# DDMTD.net
KiCad netlist of a schematic drawn in Altium Designer
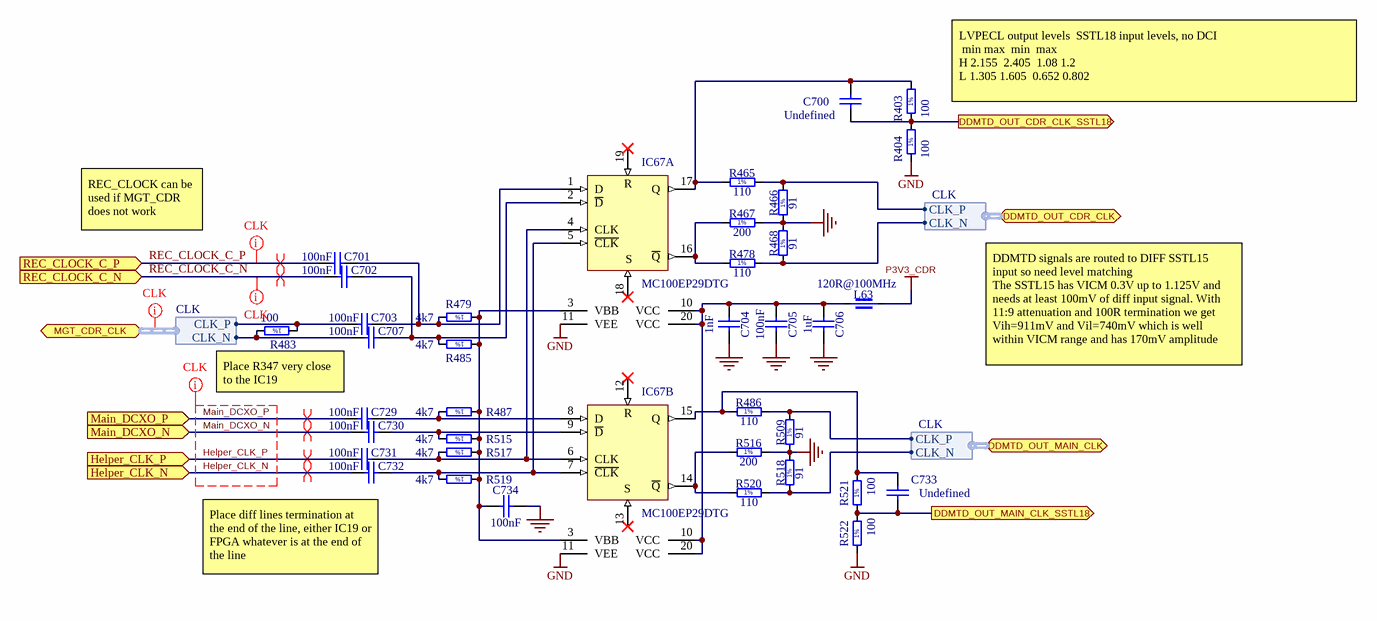
[diagram p0: DDMTD.SchDoc]

(export (version "E")
  (design (tool "Eeschema 10.0.6"))
  (components
    (comp (ref "C700")
      (value "Undefined")
      (footprint "CAPC1005X55N")
      (description "Non-polarised capacitor")
      (fields (field (name "PART NUMBER") "CC0402_NO-VALUE") (field (name "AUTHOR") "CERN DEM JLC"))
      (libsource (lib "Capacitors") (part "Capacitor - non polarized"))
    )
    (comp (ref "C701")
      (value "100nF")
      (footprint "CAPC1005X55N")
      (description "Non-polarised capacitor")
      (fields
        (field (name "MANUFACTURER PART NUMBER") "CC0402_100NF_16V_10%_X5R")
        (field (name "MANUFACTURER") "GENERIC")
        (field (name "AUTHOR") "CERN DEM JLC")
      )
      (libsource (lib "Capacitors") (part "Capacitor - non polarized"))
    )
    (comp (ref "C702")
      (value "100nF")
      (footprint "CAPC1005X55N")
      (description "Non-polarised capacitor")
      (fields
        (field (name "MANUFACTURER PART NUMBER") "CC0402_100NF_16V_10%_X5R")
        (field (name "MANUFACTURER") "GENERIC")
        (field (name "AUTHOR") "CERN DEM JLC")
      )
      (libsource (lib "Capacitors") (part "Capacitor - non polarized"))
    )
    (comp (ref "C703")
      (value "100nF")
      (footprint "CAPC1005X55N")
      (description "Non-polarised capacitor")
      (fields
        (field (name "MANUFACTURER PART NUMBER") "CC0402_100NF_16V_10%_X5R")
        (field (name "MANUFACTURER") "GENERIC")
        (field (name "AUTHOR") "CERN DEM JLC")
      )
      (libsource (lib "Capacitors") (part "Capacitor - non polarized"))
    )
    (comp (ref "C704")
      (value "1nF")
      (footprint "CAPC0603X33N")
      (description "Non-polarised capacitor")
      (fields
        (field (name "MANUFACTURER PART NUMBER") "CC0201_1NF_16V_10%_X5R")
        (field (name "MANUFACTURER") "GENERIC")
        (field (name "AUTHOR") "CERN DEM JLC")
      )
      (libsource (lib "Capacitors") (part "Capacitor - non polarized"))
    )
    (comp (ref "C705")
      (value "100nF")
      (footprint "CAPC0603X33N")
      (description "Non-polarised capacitor")
      (fields
        (field (name "MANUFACTURER PART NUMBER") "CC0201_100NF_6.3V_10%_X5R")
        (field (name "MANUFACTURER") "GENERIC")
        (field (name "AUTHOR") "CERN DEM JLC")
      )
      (libsource (lib "Capacitors") (part "Capacitor - non polarized"))
    )
    (comp (ref "C706")
      (value "1uF")
      (footprint "CAPC1005X55N")
      (description "Non-polarised capacitor")
      (fields
        (field (name "MANUFACTURER PART NUMBER") "CC0402_1UF_16V_10%_X5R")
        (field (name "MANUFACTURER") "GENERIC")
        (field (name "AUTHOR") "CERN DEM JLC")
      )
      (libsource (lib "Capacitors") (part "Capacitor - non polarized"))
    )
    (comp (ref "C707")
      (value "100nF")
      (footprint "CAPC1005X55N")
      (description "Non-polarised capacitor")
      (fields
        (field (name "MANUFACTURER PART NUMBER") "CC0402_100NF_16V_10%_X5R")
        (field (name "MANUFACTURER") "GENERIC")
        (field (name "AUTHOR") "CERN DEM JLC")
      )
      (libsource (lib "Capacitors") (part "Capacitor - non polarized"))
    )
    (comp (ref "C729")
      (value "100nF")
      (footprint "CAPC1005X55N")
      (description "Non-polarised capacitor")
      (fields
        (field (name "MANUFACTURER PART NUMBER") "CC0402_100NF_16V_10%_X5R")
        (field (name "MANUFACTURER") "GENERIC")
        (field (name "AUTHOR") "CERN DEM JLC")
      )
      (libsource (lib "Capacitors") (part "Capacitor - non polarized"))
    )
    (comp (ref "C730")
      (value "100nF")
      (footprint "CAPC1005X55N")
      (description "Non-polarised capacitor")
      (fields
        (field (name "MANUFACTURER PART NUMBER") "CC0402_100NF_16V_10%_X5R")
        (field (name "MANUFACTURER") "GENERIC")
        (field (name "AUTHOR") "CERN DEM JLC")
      )
      (libsource (lib "Capacitors") (part "Capacitor - non polarized"))
    )
    (comp (ref "C731")
      (value "100nF")
      (footprint "CAPC1005X55N")
      (description "Non-polarised capacitor")
      (fields
        (field (name "MANUFACTURER PART NUMBER") "CC0402_100NF_16V_10%_X5R")
        (field (name "MANUFACTURER") "GENERIC")
        (field (name "AUTHOR") "CERN DEM JLC")
      )
      (libsource (lib "Capacitors") (part "Capacitor - non polarized"))
    )
    (comp (ref "C732")
      (value "100nF")
      (footprint "CAPC1005X55N")
      (description "Non-polarised capacitor")
      (fields
        (field (name "MANUFACTURER PART NUMBER") "CC0402_100NF_16V_10%_X5R")
        (field (name "MANUFACTURER") "GENERIC")
        (field (name "AUTHOR") "CERN DEM JLC")
      )
      (libsource (lib "Capacitors") (part "Capacitor - non polarized"))
    )
    (comp (ref "C733")
      (value "Undefined")
      (footprint "CAPC1005X55N")
      (description "Non-polarised capacitor")
      (fields (field (name "PART NUMBER") "CC0402_NO-VALUE") (field (name "AUTHOR") "CERN DEM JLC"))
      (libsource (lib "Capacitors") (part "Capacitor - non polarized"))
    )
    (comp (ref "C734")
      (value "100nF")
      (footprint "CAPC0603X33N")
      (description "Non-polarised capacitor")
      (fields
        (field (name "MANUFACTURER PART NUMBER") "CC0201_100NF_6.3V_10%_X5R")
        (field (name "MANUFACTURER") "GENERIC")
        (field (name "AUTHOR") "CERN DEM JLC")
      )
      (libsource (lib "Capacitors") (part "Capacitor - non polarized"))
    )
    (comp (ref "IC67")
      (value "MC100EP29DTG")
      (footprint "SOP65P640X120-20N")
      (description "3.3V/5V ECL Dual Differential Data and Clock D Flip-Flop With Set and Reset")
      (fields (field (name "MANUFACTURER") "ON SEMICONDUCTOR") (field (name "AUTHOR") "CERN DEM JLC"))
      (libsource (lib "ICs And Semiconductors") (part "100EP29D"))
    )
    (comp (ref "L63")
      (value "120R@100MHz")
      (footprint "INDC1608X95N")
      (fields
        (field (name "MANUFACTURER PART NUMBER") "BLM18PG121SN1D")
        (field (name "MANUFACTURER") "MURATA")
        (field (name "PART NUMBER") "IND0603_MURATA_BLM18PG121SN1D")
        (field (name "AUTHOR") "CERN DEM BC")
      )
      (libsource (lib "Inductors & Transformers") (part "Ferrite Bead"))
    )
    (comp (ref "R403")
      (value "100")
      (footprint "RESC1005X40N")
      (description "Resistor - 1%")
      (fields
        (field (name "MANUFACTURER PART NUMBER") "R0402_100R_1%_0.0625W_100PPM")
        (field (name "MANUFACTURER") "GENERIC")
        (field (name "AUTHOR") "CERN DEM JLC")
      )
      (libsource (lib "Resistors") (part "Resistor - 1%"))
    )
    (comp (ref "R404")
      (value "100")
      (footprint "RESC1005X40N")
      (description "Resistor - 1%")
      (fields
        (field (name "MANUFACTURER PART NUMBER") "R0402_100R_1%_0.0625W_100PPM")
        (field (name "MANUFACTURER") "GENERIC")
        (field (name "AUTHOR") "CERN DEM JLC")
      )
      (libsource (lib "Resistors") (part "Resistor - 1%"))
    )
    (comp (ref "R465")
      (value "110")
      (footprint "RESC1005X40N")
      (description "Resistor - 1%")
      (fields
        (field (name "MANUFACTURER PART NUMBER") "R0402_110R_1%_0.0625W_100PPM")
        (field (name "MANUFACTURER") "GENERIC")
        (field (name "AUTHOR") "CERN DEM JLC")
      )
      (libsource (lib "Resistors") (part "Resistor - 1%"))
    )
    (comp (ref "R466")
      (value "91")
      (footprint "RESC1005X40N")
      (description "Resistor - 1%")
      (fields
        (field (name "MANUFACTURER PART NUMBER") "R0402_91R_1%_0.0625W_100PPM")
        (field (name "MANUFACTURER") "GENERIC")
        (field (name "AUTHOR") "CERN DEM JLC")
      )
      (libsource (lib "Resistors") (part "Resistor - 1%"))
    )
    (comp (ref "R467")
      (value "200")
      (footprint "RESC1005X40N")
      (description "Resistor - 1%")
      (fields
        (field (name "PART NUMBER") "R0402_200R_1%_0.0625W_100PPM")
        (field (name "POWER") "0.0625W")
        (field (name "AUTHOR") "CERN DEM JLC")
      )
      (libsource (lib "Resistors") (part "Resistor - 1%"))
    )
    (comp (ref "R468")
      (value "91")
      (footprint "RESC1005X40N")
      (description "Resistor - 1%")
      (fields
        (field (name "MANUFACTURER PART NUMBER") "R0402_91R_1%_0.0625W_100PPM")
        (field (name "MANUFACTURER") "GENERIC")
        (field (name "AUTHOR") "CERN DEM JLC")
      )
      (libsource (lib "Resistors") (part "Resistor - 1%"))
    )
    (comp (ref "R478")
      (value "110")
      (footprint "RESC1005X40N")
      (description "Resistor - 1%")
      (fields
        (field (name "MANUFACTURER PART NUMBER") "R0402_110R_1%_0.0625W_100PPM")
        (field (name "MANUFACTURER") "GENERIC")
        (field (name "AUTHOR") "CERN DEM JLC")
      )
      (libsource (lib "Resistors") (part "Resistor - 1%"))
    )
    (comp (ref "R479")
      (value "4k7")
      (footprint "RESC1005X40N")
      (description "Resistor - 1%")
      (fields
        (field (name "MANUFACTURER PART NUMBER") "R0402_4K7_1%_0.0625W_100PPM")
        (field (name "MANUFACTURER") "GENERIC")
        (field (name "AUTHOR") "CERN DEM JLC")
      )
      (libsource (lib "Resistors") (part "Resistor - 1%"))
    )
    (comp (ref "R483")
      (value "100")
      (footprint "RESC1005X40N")
      (description "Resistor - 1%")
      (fields
        (field (name "MANUFACTURER PART NUMBER") "R0402_100R_1%_0.0625W_100PPM")
        (field (name "MANUFACTURER") "GENERIC")
        (field (name "AUTHOR") "CERN DEM JLC")
      )
      (libsource (lib "Resistors") (part "Resistor - 1%"))
    )
    (comp (ref "R485")
      (value "4k7")
      (footprint "RESC1005X40N")
      (description "Resistor - 1%")
      (fields
        (field (name "MANUFACTURER PART NUMBER") "R0402_4K7_1%_0.0625W_100PPM")
        (field (name "MANUFACTURER") "GENERIC")
        (field (name "AUTHOR") "CERN DEM JLC")
      )
      (libsource (lib "Resistors") (part "Resistor - 1%"))
    )
    (comp (ref "R486")
      (value "110")
      (footprint "RESC1005X40N")
      (description "Resistor - 1%")
      (fields
        (field (name "MANUFACTURER PART NUMBER") "R0402_110R_1%_0.0625W_100PPM")
        (field (name "MANUFACTURER") "GENERIC")
        (field (name "AUTHOR") "CERN DEM JLC")
      )
      (libsource (lib "Resistors") (part "Resistor - 1%"))
    )
    (comp (ref "R487")
      (value "4k7")
      (footprint "RESC1005X40N")
      (description "Resistor - 1%")
      (fields
        (field (name "MANUFACTURER PART NUMBER") "R0402_4K7_1%_0.0625W_100PPM")
        (field (name "MANUFACTURER") "GENERIC")
        (field (name "AUTHOR") "CERN DEM JLC")
      )
      (libsource (lib "Resistors") (part "Resistor - 1%"))
    )
    (comp (ref "R509")
      (value "91")
      (footprint "RESC1005X40N")
      (description "Resistor - 1%")
      (fields
        (field (name "MANUFACTURER PART NUMBER") "R0402_91R_1%_0.0625W_100PPM")
        (field (name "MANUFACTURER") "GENERIC")
        (field (name "AUTHOR") "CERN DEM JLC")
      )
      (libsource (lib "Resistors") (part "Resistor - 1%"))
    )
    (comp (ref "R515")
      (value "4k7")
      (footprint "RESC1005X40N")
      (description "Resistor - 1%")
      (fields
        (field (name "MANUFACTURER PART NUMBER") "R0402_4K7_1%_0.0625W_100PPM")
        (field (name "MANUFACTURER") "GENERIC")
        (field (name "AUTHOR") "CERN DEM JLC")
      )
      (libsource (lib "Resistors") (part "Resistor - 1%"))
    )
    (comp (ref "R516")
      (value "200")
      (footprint "RESC1005X40N")
      (description "Resistor - 1%")
      (fields
        (field (name "PART NUMBER") "R0402_200R_1%_0.0625W_100PPM")
        (field (name "POWER") "0.0625W")
        (field (name "AUTHOR") "CERN DEM JLC")
      )
      (libsource (lib "Resistors") (part "Resistor - 1%"))
    )
    (comp (ref "R517")
      (value "4k7")
      (footprint "RESC1005X40N")
      (description "Resistor - 1%")
      (fields
        (field (name "MANUFACTURER PART NUMBER") "R0402_4K7_1%_0.0625W_100PPM")
        (field (name "MANUFACTURER") "GENERIC")
        (field (name "AUTHOR") "CERN DEM JLC")
      )
      (libsource (lib "Resistors") (part "Resistor - 1%"))
    )
    (comp (ref "R518")
      (value "91")
      (footprint "RESC1005X40N")
      (description "Resistor - 1%")
      (fields
        (field (name "MANUFACTURER PART NUMBER") "R0402_91R_1%_0.0625W_100PPM")
        (field (name "MANUFACTURER") "GENERIC")
        (field (name "AUTHOR") "CERN DEM JLC")
      )
      (libsource (lib "Resistors") (part "Resistor - 1%"))
    )
    (comp (ref "R519")
      (value "4k7")
      (footprint "RESC1005X40N")
      (description "Resistor - 1%")
      (fields
        (field (name "MANUFACTURER PART NUMBER") "R0402_4K7_1%_0.0625W_100PPM")
        (field (name "MANUFACTURER") "GENERIC")
        (field (name "AUTHOR") "CERN DEM JLC")
      )
      (libsource (lib "Resistors") (part "Resistor - 1%"))
    )
    (comp (ref "R520")
      (value "110")
      (footprint "RESC1005X40N")
      (description "Resistor - 1%")
      (fields
        (field (name "MANUFACTURER PART NUMBER") "R0402_110R_1%_0.0625W_100PPM")
        (field (name "MANUFACTURER") "GENERIC")
        (field (name "AUTHOR") "CERN DEM JLC")
      )
      (libsource (lib "Resistors") (part "Resistor - 1%"))
    )
    (comp (ref "R521")
      (value "100")
      (footprint "RESC1005X40N")
      (description "Resistor - 1%")
      (fields
        (field (name "MANUFACTURER PART NUMBER") "R0402_100R_1%_0.0625W_100PPM")
        (field (name "MANUFACTURER") "GENERIC")
        (field (name "AUTHOR") "CERN DEM JLC")
      )
      (libsource (lib "Resistors") (part "Resistor - 1%"))
    )
    (comp (ref "R522")
      (value "100")
      (footprint "RESC1005X40N")
      (description "Resistor - 1%")
      (fields
        (field (name "MANUFACTURER PART NUMBER") "R0402_100R_1%_0.0625W_100PPM")
        (field (name "MANUFACTURER") "GENERIC")
        (field (name "AUTHOR") "CERN DEM JLC")
      )
      (libsource (lib "Resistors") (part "Resistor - 1%"))
    )
  )
  (nets
    (net (code "2") (name "/DDMTD_OUT_CDR_CLK_SSTL18") (class "Default")
      (node (ref "C700") (pin "1") (pinfunction "1_1") (pintype "passive"))
      (node (ref "R403") (pin "1") (pinfunction "1_1") (pintype "passive"))
      (node (ref "R404") (pin "2") (pinfunction "2_2") (pintype "passive"))
    )
    (net (code "3") (name "/DDMTD_OUT_MAIN_CLK_SSTL18") (class "Default")
      (node (ref "C733") (pin "1") (pinfunction "1_1") (pintype "passive"))
      (node (ref "R521") (pin "1") (pinfunction "1_1") (pintype "passive"))
      (node (ref "R522") (pin "2") (pinfunction "2_2") (pintype "passive"))
    )
    (net (code "4") (name "/Helper_CLK_N") (class "Default")
      (node (ref "C732") (pin "1") (pinfunction "1_1") (pintype "passive"))
    )
    (net (code "5") (name "/Helper_CLK_P") (class "Default")
      (node (ref "C731") (pin "1") (pinfunction "1_1") (pintype "passive"))
    )
    (net (code "6") (name "/Main_DCXO_N") (class "Default")
      (node (ref "C730") (pin "1") (pinfunction "1_1") (pintype "passive"))
    )
    (net (code "7") (name "/Main_DCXO_P") (class "Default")
      (node (ref "C729") (pin "1") (pinfunction "1_1") (pintype "passive"))
    )
    (net (code "8") (name "/REC_CLOCK_C_N") (class "Default")
      (node (ref "C702") (pin "1") (pinfunction "1_1") (pintype "passive"))
    )
    (net (code "9") (name "/REC_CLOCK_C_P") (class "Default")
      (node (ref "C701") (pin "1") (pinfunction "1_1") (pintype "passive"))
    )
    (net (code "11") (name "GND") (class "Default")
      (node (ref "C704") (pin "1") (pinfunction "1_1") (pintype "passive"))
      (node (ref "C705") (pin "1") (pinfunction "1_1") (pintype "passive"))
      (node (ref "C706") (pin "2") (pinfunction "2_2") (pintype "passive"))
      (node (ref "C734") (pin "1") (pinfunction "1_1") (pintype "passive"))
      (node (ref "IC67") (pin "11") (pinfunction "VEE_11") (pintype "power_in"))
      (node (ref "R404") (pin "1") (pinfunction "1_1") (pintype "passive"))
      (node (ref "R466") (pin "1") (pinfunction "1_1") (pintype "passive"))
      (node (ref "R467") (pin "2") (pinfunction "2_2") (pintype "passive"))
      (node (ref "R468") (pin "2") (pinfunction "2_2") (pintype "passive"))
      (node (ref "R509") (pin "1") (pinfunction "1_1") (pintype "passive"))
      (node (ref "R516") (pin "2") (pinfunction "2_2") (pintype "passive"))
      (node (ref "R518") (pin "2") (pinfunction "2_2") (pintype "passive"))
      (node (ref "R522") (pin "1") (pinfunction "1_1") (pintype "passive"))
    )
    (net (code "12") (name "Net-(C703-Pad1)") (class "Default")
      (node (ref "C703") (pin "1") (pinfunction "1_1") (pintype "passive"))
      (node (ref "R483") (pin "1") (pinfunction "1_1") (pintype "passive"))
    )
    (net (code "13") (name "Net-(C704-Pad2)") (class "Default")
      (node (ref "C704") (pin "2") (pinfunction "2_2") (pintype "passive"))
      (node (ref "C705") (pin "2") (pinfunction "2_2") (pintype "passive"))
      (node (ref "C706") (pin "1") (pinfunction "1_1") (pintype "passive"))
      (node (ref "IC67") (pin "10") (pinfunction "VCC_10") (pintype "power_in"))
      (node (ref "IC67") (pin "20") (pinfunction "VCC_20") (pintype "power_in"))
      (node (ref "L63") (pin "2") (pinfunction "2_2") (pintype "passive"))
    )
    (net (code "14") (name "Net-(C707-Pad1)") (class "Default")
      (node (ref "C707") (pin "1") (pinfunction "1_1") (pintype "passive"))
      (node (ref "R483") (pin "2") (pinfunction "2_2") (pintype "passive"))
    )
    (net (code "15") (name "Net-(IC67A-CLK)") (class "Default")
      (node (ref "C731") (pin "2") (pinfunction "2_2") (pintype "passive"))
      (node (ref "IC67") (pin "4") (pinfunction "CLK_4") (pintype "input"))
      (node (ref "IC67") (pin "6") (pinfunction "CLK_6") (pintype "input"))
      (node (ref "R517") (pin "2") (pinfunction "2_2") (pintype "passive"))
    )
    (net (code "16") (name "Net-(IC67A-D)") (class "Default")
      (node (ref "C701") (pin "2") (pinfunction "2_2") (pintype "passive"))
      (node (ref "C703") (pin "2") (pinfunction "2_2") (pintype "passive"))
      (node (ref "IC67") (pin "1") (pinfunction "D_1") (pintype "input"))
      (node (ref "R479") (pin "2") (pinfunction "2_2") (pintype "passive"))
    )
    (net (code "17") (name "Net-(IC67A-Q)") (class "Default")
      (node (ref "C700") (pin "2") (pinfunction "2_2") (pintype "passive"))
      (node (ref "IC67") (pin "17") (pinfunction "Q_17") (pintype "output"))
      (node (ref "R403") (pin "2") (pinfunction "2_2") (pintype "passive"))
      (node (ref "R465") (pin "1") (pinfunction "1_1") (pintype "passive"))
    )
    (net (code "18") (name "Net-(IC67A-VBB)") (class "Default")
      (node (ref "C734") (pin "2") (pinfunction "2_2") (pintype "passive"))
      (node (ref "IC67") (pin "3") (pinfunction "VBB_3") (pintype "power_in"))
      (node (ref "R479") (pin "1") (pinfunction "1_1") (pintype "passive"))
      (node (ref "R485") (pin "1") (pinfunction "1_1") (pintype "passive"))
      (node (ref "R487") (pin "1") (pinfunction "1_1") (pintype "passive"))
      (node (ref "R515") (pin "1") (pinfunction "1_1") (pintype "passive"))
      (node (ref "R517") (pin "1") (pinfunction "1_1") (pintype "passive"))
      (node (ref "R519") (pin "1") (pinfunction "1_1") (pintype "passive"))
    )
    (net (code "19") (name "Net-(IC67A-~{CLK})") (class "Default")
      (node (ref "C732") (pin "2") (pinfunction "2_2") (pintype "passive"))
      (node (ref "IC67") (pin "5") (pinfunction "~{CLK}_5") (pintype "input"))
      (node (ref "IC67") (pin "7") (pinfunction "~{CLK}_7") (pintype "input"))
      (node (ref "R519") (pin "2") (pinfunction "2_2") (pintype "passive"))
    )
    (net (code "20") (name "Net-(IC67A-~{D})") (class "Default")
      (node (ref "C702") (pin "2") (pinfunction "2_2") (pintype "passive"))
      (node (ref "C707") (pin "2") (pinfunction "2_2") (pintype "passive"))
      (node (ref "IC67") (pin "2") (pinfunction "~{D}_2") (pintype "input"))
      (node (ref "R485") (pin "2") (pinfunction "2_2") (pintype "passive"))
    )
    (net (code "21") (name "Net-(IC67A-~{Q})") (class "Default")
      (node (ref "IC67") (pin "16") (pinfunction "~{Q}_16") (pintype "output"))
      (node (ref "R467") (pin "1") (pinfunction "1_1") (pintype "passive"))
      (node (ref "R478") (pin "1") (pinfunction "1_1") (pintype "passive"))
    )
    (net (code "22") (name "Net-(IC67B-D)") (class "Default")
      (node (ref "C729") (pin "2") (pinfunction "2_2") (pintype "passive"))
      (node (ref "IC67") (pin "8") (pinfunction "D_8") (pintype "input"))
      (node (ref "R487") (pin "2") (pinfunction "2_2") (pintype "passive"))
    )
    (net (code "23") (name "Net-(IC67B-Q)") (class "Default")
      (node (ref "C733") (pin "2") (pinfunction "2_2") (pintype "passive"))
      (node (ref "IC67") (pin "15") (pinfunction "Q_15") (pintype "output"))
      (node (ref "R486") (pin "1") (pinfunction "1_1") (pintype "passive"))
      (node (ref "R521") (pin "2") (pinfunction "2_2") (pintype "passive"))
    )
    (net (code "24") (name "Net-(IC67B-~{D})") (class "Default")
      (node (ref "C730") (pin "2") (pinfunction "2_2") (pintype "passive"))
      (node (ref "IC67") (pin "9") (pinfunction "~{D}_9") (pintype "input"))
      (node (ref "R515") (pin "2") (pinfunction "2_2") (pintype "passive"))
    )
    (net (code "25") (name "Net-(IC67B-~{Q})") (class "Default")
      (node (ref "IC67") (pin "14") (pinfunction "~{Q}_14") (pintype "output"))
      (node (ref "R516") (pin "1") (pinfunction "1_1") (pintype "passive"))
      (node (ref "R520") (pin "1") (pinfunction "1_1") (pintype "passive"))
    )
    (net (code "26") (name "Net-(R465-Pad2)") (class "Default")
      (node (ref "R465") (pin "2") (pinfunction "2_2") (pintype "passive"))
      (node (ref "R466") (pin "2") (pinfunction "2_2") (pintype "passive"))
    )
    (net (code "27") (name "Net-(R468-Pad1)") (class "Default")
      (node (ref "R468") (pin "1") (pinfunction "1_1") (pintype "passive"))
      (node (ref "R478") (pin "2") (pinfunction "2_2") (pintype "passive"))
    )
    (net (code "28") (name "Net-(R486-Pad2)") (class "Default")
      (node (ref "R486") (pin "2") (pinfunction "2_2") (pintype "passive"))
      (node (ref "R509") (pin "2") (pinfunction "2_2") (pintype "passive"))
    )
    (net (code "29") (name "Net-(R518-Pad1)") (class "Default")
      (node (ref "R518") (pin "1") (pinfunction "1_1") (pintype "passive"))
      (node (ref "R520") (pin "2") (pinfunction "2_2") (pintype "passive"))
    )
    (net (code "30") (name "P3V3_CDR") (class "Default")
      (node (ref "L63") (pin "1") (pinfunction "1_1") (pintype "passive"))
    )
    (net (code "31") (name "unconnected-(IC67A-R-Pad19)") (class "Default")
      (node (ref "IC67") (pin "19") (pinfunction "R_19") (pintype "input+no_connect"))
    )
    (net (code "32") (name "unconnected-(IC67A-S-Pad18)") (class "Default")
      (node (ref "IC67") (pin "18") (pinfunction "S_18") (pintype "input+no_connect"))
    )
    (net (code "33") (name "unconnected-(IC67B-R-Pad12)") (class "Default")
      (node (ref "IC67") (pin "12") (pinfunction "R_12") (pintype "input+no_connect"))
    )
    (net (code "34") (name "unconnected-(IC67B-S-Pad13)") (class "Default")
      (node (ref "IC67") (pin "13") (pinfunction "S_13") (pintype "input+no_connect"))
    )
  )
)
